# Nixie.net
KiCad netlist of a schematic drawn in EAGLE
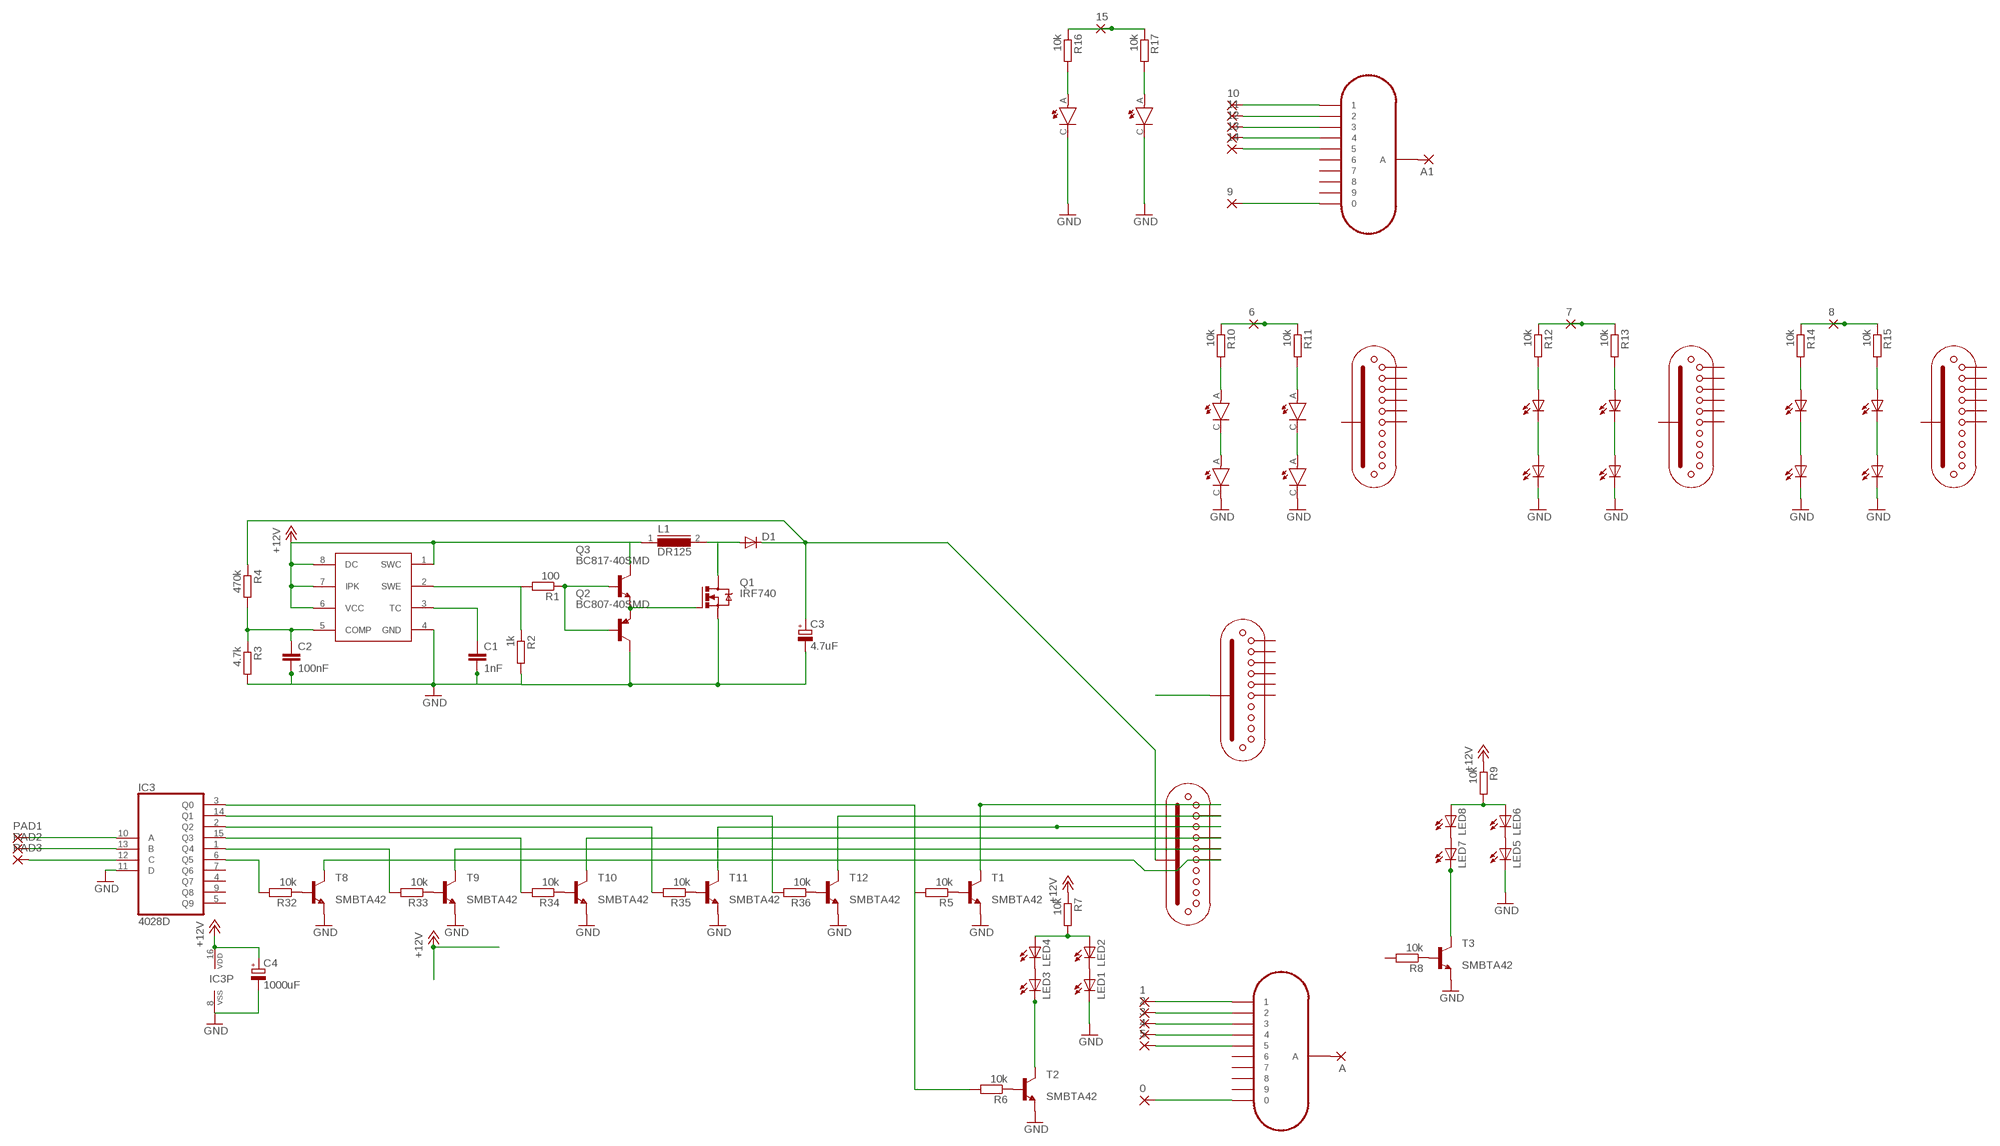
[diagram p0: schematic, sheet 1]

(export (version "E")
  (design (tool "Eeschema 10.0.6"))
  (components
    (comp (ref "0")
      (value "SMD2")
      (footprint "eagle-import:SMD1,27-2,54")
      (libsource (lib "eagle-import") (part "SMD2"))
    )
    (comp (ref "1")
      (value "SMD2")
      (footprint "eagle-import:SMD1,27-2,54")
      (libsource (lib "eagle-import") (part "SMD2"))
    )
    (comp (ref "2")
      (value "SMD2")
      (footprint "eagle-import:SMD1,27-2,54")
      (libsource (lib "eagle-import") (part "SMD2"))
    )
    (comp (ref "3")
      (value "SMD2")
      (footprint "eagle-import:SMD1,27-2,54")
      (libsource (lib "eagle-import") (part "SMD2"))
    )
    (comp (ref "4")
      (value "SMD2")
      (footprint "eagle-import:SMD1,27-2,54")
      (libsource (lib "eagle-import") (part "SMD2"))
    )
    (comp (ref "5")
      (value "SMD2")
      (footprint "eagle-import:SMD1,27-2,54")
      (libsource (lib "eagle-import") (part "SMD2"))
    )
    (comp (ref "6")
      (value "SMD2")
      (footprint "eagle-import:SMD1,27-2,54")
      (libsource (lib "eagle-import") (part "SMD2"))
    )
    (comp (ref "7")
      (value "SMD2")
      (footprint "eagle-import:SMD1,27-2,54")
      (libsource (lib "eagle-import") (part "SMD2"))
    )
    (comp (ref "8")
      (value "SMD2")
      (footprint "eagle-import:SMD1,27-2,54")
      (libsource (lib "eagle-import") (part "SMD2"))
    )
    (comp (ref "9")
      (value "SMD2")
      (footprint "eagle-import:SMD1,27-2,54")
      (libsource (lib "eagle-import") (part "SMD2"))
    )
    (comp (ref "10")
      (value "SMD2")
      (footprint "eagle-import:SMD1,27-2,54")
      (libsource (lib "eagle-import") (part "SMD2"))
    )
    (comp (ref "11")
      (value "SMD2")
      (footprint "eagle-import:SMD1,27-2,54")
      (libsource (lib "eagle-import") (part "SMD2"))
    )
    (comp (ref "12")
      (value "SMD2")
      (footprint "eagle-import:SMD1,27-2,54")
      (libsource (lib "eagle-import") (part "SMD2"))
    )
    (comp (ref "13")
      (value "SMD2")
      (footprint "eagle-import:SMD1,27-2,54")
      (libsource (lib "eagle-import") (part "SMD2"))
    )
    (comp (ref "14")
      (value "SMD2")
      (footprint "eagle-import:SMD1,27-2,54")
      (libsource (lib "eagle-import") (part "SMD2"))
    )
    (comp (ref "15")
      (value "SMD2")
      (footprint "eagle-import:SMD1,27-2,54")
      (libsource (lib "eagle-import") (part "SMD2"))
    )
    (comp (ref "A")
      (value "SMD2")
      (footprint "eagle-import:SMD1,27-2,54")
      (libsource (lib "eagle-import") (part "SMD2"))
    )
    (comp (ref "A1")
      (value "SMD2")
      (footprint "eagle-import:SMD1,27-2,54")
      (libsource (lib "eagle-import") (part "SMD2"))
    )
    (comp (ref "C1")
      (value "1nF")
      (footprint "eagle-import:C0805K")
      (libsource (lib "eagle-import") (part "C-EUC0805K"))
    )
    (comp (ref "C2")
      (value "100nF")
      (footprint "eagle-import:C0805K")
      (libsource (lib "eagle-import") (part "C-EUC0805K"))
    )
    (comp (ref "C3")
      (value "4.7uF")
      (footprint "eagle-import:E5-10,5")
      (libsource (lib "eagle-import") (part "CPOL-EUE5-10.5"))
    )
    (comp (ref "C4")
      (value "1000uF")
      (footprint "eagle-import:E5-10,5")
      (libsource (lib "eagle-import") (part "CPOL-EUE5-10.5"))
    )
    (comp (ref "D1")
      (value "DIODE-DO214AC")
      (footprint "eagle-import:DO214AC")
      (libsource (lib "eagle-import") (part "DIODE-DO214AC"))
    )
    (comp (ref "IC3")
      (value "4028D")
      (footprint "eagle-import:SO16")
      (libsource (lib "eagle-import") (part "4028D"))
    )
    (comp (ref "L1")
      (value "DR125")
      (footprint "eagle-import:DR125")
      (libsource (lib "eagle-import") (part "DR125"))
    )
    (comp (ref "LED1")
      (value "LED3MM")
      (footprint "eagle-import:LED3MM")
      (libsource (lib "eagle-import") (part "LED3MM"))
    )
    (comp (ref "LED2")
      (value "LED3MM")
      (footprint "eagle-import:LED3MM")
      (libsource (lib "eagle-import") (part "LED3MM"))
    )
    (comp (ref "LED3")
      (value "LED3MM")
      (footprint "eagle-import:LED3MM")
      (libsource (lib "eagle-import") (part "LED3MM"))
    )
    (comp (ref "LED4")
      (value "LED3MM")
      (footprint "eagle-import:LED3MM")
      (libsource (lib "eagle-import") (part "LED3MM"))
    )
    (comp (ref "LED5")
      (value "LED3MM")
      (footprint "eagle-import:LED3MM")
      (libsource (lib "eagle-import") (part "LED3MM"))
    )
    (comp (ref "LED6")
      (value "LED3MM")
      (footprint "eagle-import:LED3MM")
      (libsource (lib "eagle-import") (part "LED3MM"))
    )
    (comp (ref "LED7")
      (value "LED3MM")
      (footprint "eagle-import:LED3MM")
      (libsource (lib "eagle-import") (part "LED3MM"))
    )
    (comp (ref "LED8")
      (value "LED3MM")
      (footprint "eagle-import:LED3MM")
      (libsource (lib "eagle-import") (part "LED3MM"))
    )
    (comp (ref "LED9")
      (value "LED_PLCC6")
      (footprint "eagle-import:PLCC6")
      (libsource (lib "eagle-import") (part "LED_PLCC6"))
    )
    (comp (ref "LED10")
      (value "LED_PLCC6")
      (footprint "eagle-import:PLCC6")
      (libsource (lib "eagle-import") (part "LED_PLCC6"))
    )
    (comp (ref "LED11")
      (value "LED_PLCC6")
      (footprint "eagle-import:PLCC6")
      (libsource (lib "eagle-import") (part "LED_PLCC6"))
    )
    (comp (ref "LED12")
      (value "LED_PLCC6")
      (footprint "eagle-import:PLCC6")
      (libsource (lib "eagle-import") (part "LED_PLCC6"))
    )
    (comp (ref "LED13")
      (value "LED_LRTB_G6TG")
      (footprint "eagle-import:PLCC6")
      (libsource (lib "eagle-import") (part "LED_LRTB_G6TG"))
    )
    (comp (ref "LED14")
      (value "LED_LRTB_G6TG")
      (footprint "eagle-import:PLCC6")
      (libsource (lib "eagle-import") (part "LED_LRTB_G6TG"))
    )
    (comp (ref "N1")
      (value "IN-12A-IN-12")
      (footprint "eagle-import:IN-12")
      (libsource (lib "eagle-import") (part "IN-12A-IN-12"))
    )
    (comp (ref "N2")
      (value "IN-12A-IN-12")
      (footprint "eagle-import:IN-12")
      (libsource (lib "eagle-import") (part "IN-12A-IN-12"))
    )
    (comp (ref "PAD1")
      (value "1,6/0,8")
      (footprint "eagle-import:1,6_0,8")
      (libsource (lib "eagle-import") (part "1,6/0,8"))
    )
    (comp (ref "PAD2")
      (value "1,6/0,8")
      (footprint "eagle-import:1,6_0,8")
      (libsource (lib "eagle-import") (part "1,6/0,8"))
    )
    (comp (ref "PAD3")
      (value "1,6/0,8")
      (footprint "eagle-import:1,6_0,8")
      (libsource (lib "eagle-import") (part "1,6/0,8"))
    )
    (comp (ref "Q1")
      (value "IRF740")
      (footprint "eagle-import:TO220BV")
      (libsource (lib "eagle-import") (part "IRF740"))
    )
    (comp (ref "Q2")
      (value "BC807-40SMD")
      (footprint "eagle-import:SOT23-BEC")
      (libsource (lib "eagle-import") (part "BC807SMD-40"))
    )
    (comp (ref "Q3")
      (value "BC817-40SMD")
      (footprint "eagle-import:SOT23-BEC")
      (libsource (lib "eagle-import") (part "BC817SMD-40"))
    )
    (comp (ref "R1")
      (value "100")
      (footprint "eagle-import:R0805")
      (libsource (lib "eagle-import") (part "R-EU_R0805"))
    )
    (comp (ref "R2")
      (value "1k")
      (footprint "eagle-import:R0805")
      (libsource (lib "eagle-import") (part "R-EU_R0805"))
    )
    (comp (ref "R3")
      (value "4.7k")
      (footprint "eagle-import:R0805")
      (libsource (lib "eagle-import") (part "R-EU_R0805"))
    )
    (comp (ref "R4")
      (value "470k")
      (footprint "eagle-import:R0805")
      (libsource (lib "eagle-import") (part "R-EU_R0805"))
    )
    (comp (ref "R5")
      (value "10k")
      (footprint "eagle-import:R0805")
      (libsource (lib "eagle-import") (part "R-EU_R0805"))
    )
    (comp (ref "R6")
      (value "10k")
      (footprint "eagle-import:R0805")
      (libsource (lib "eagle-import") (part "R-EU_R0805"))
    )
    (comp (ref "R7")
      (value "10k")
      (footprint "eagle-import:R0805")
      (libsource (lib "eagle-import") (part "R-EU_R0805"))
    )
    (comp (ref "R8")
      (value "10k")
      (footprint "eagle-import:R0805")
      (libsource (lib "eagle-import") (part "R-EU_R0805"))
    )
    (comp (ref "R9")
      (value "10k")
      (footprint "eagle-import:R0805")
      (libsource (lib "eagle-import") (part "R-EU_R0805"))
    )
    (comp (ref "R10")
      (value "10k")
      (footprint "eagle-import:R0805")
      (libsource (lib "eagle-import") (part "R-EU_R0805"))
    )
    (comp (ref "R11")
      (value "10k")
      (footprint "eagle-import:R0805")
      (libsource (lib "eagle-import") (part "R-EU_R0805"))
    )
    (comp (ref "R12")
      (value "10k")
      (footprint "eagle-import:R0805")
      (libsource (lib "eagle-import") (part "R-EU_R0805"))
    )
    (comp (ref "R13")
      (value "10k")
      (footprint "eagle-import:R0805")
      (libsource (lib "eagle-import") (part "R-EU_R0805"))
    )
    (comp (ref "R14")
      (value "10k")
      (footprint "eagle-import:R0805")
      (libsource (lib "eagle-import") (part "R-EU_R0805"))
    )
    (comp (ref "R15")
      (value "10k")
      (footprint "eagle-import:R0805")
      (libsource (lib "eagle-import") (part "R-EU_R0805"))
    )
    (comp (ref "R16")
      (value "10k")
      (footprint "eagle-import:R0805")
      (libsource (lib "eagle-import") (part "R-EU_R0805"))
    )
    (comp (ref "R17")
      (value "10k")
      (footprint "eagle-import:R0805")
      (libsource (lib "eagle-import") (part "R-EU_R0805"))
    )
    (comp (ref "R32")
      (value "10k")
      (footprint "eagle-import:R0805")
      (libsource (lib "eagle-import") (part "R-EU_R0805"))
    )
    (comp (ref "R33")
      (value "10k")
      (footprint "eagle-import:R0805")
      (libsource (lib "eagle-import") (part "R-EU_R0805"))
    )
    (comp (ref "R34")
      (value "10k")
      (footprint "eagle-import:R0805")
      (libsource (lib "eagle-import") (part "R-EU_R0805"))
    )
    (comp (ref "R35")
      (value "10k")
      (footprint "eagle-import:R0805")
      (libsource (lib "eagle-import") (part "R-EU_R0805"))
    )
    (comp (ref "R36")
      (value "10k")
      (footprint "eagle-import:R0805")
      (libsource (lib "eagle-import") (part "R-EU_R0805"))
    )
    (comp (ref "T1")
      (value "MMBTA42LT1-NPN-SOT23-BEC")
      (footprint "eagle-import:SOT23-BEC")
      (fields (field (name "T") "SMBTA42"))
      (libsource (lib "eagle-import") (part "-NPN-SOT23-BECMMBTA42LT1"))
    )
    (comp (ref "T2")
      (value "MMBTA42LT1-NPN-SOT23-BEC")
      (footprint "eagle-import:SOT23-BEC")
      (fields (field (name "T") "SMBTA42"))
      (libsource (lib "eagle-import") (part "-NPN-SOT23-BECMMBTA42LT1"))
    )
    (comp (ref "T3")
      (value "MMBTA42LT1-NPN-SOT23-BEC")
      (footprint "eagle-import:SOT23-BEC")
      (fields (field (name "T") "SMBTA42"))
      (libsource (lib "eagle-import") (part "-NPN-SOT23-BECMMBTA42LT1"))
    )
    (comp (ref "T8")
      (value "MMBTA42LT1-NPN-SOT23-BEC")
      (footprint "eagle-import:SOT23-BEC")
      (fields (field (name "T") "SMBTA42"))
      (libsource (lib "eagle-import") (part "-NPN-SOT23-BECMMBTA42LT1"))
    )
    (comp (ref "T9")
      (value "MMBTA42LT1-NPN-SOT23-BEC")
      (footprint "eagle-import:SOT23-BEC")
      (fields (field (name "T") "SMBTA42"))
      (libsource (lib "eagle-import") (part "-NPN-SOT23-BECMMBTA42LT1"))
    )
    (comp (ref "T10")
      (value "MMBTA42LT1-NPN-SOT23-BEC")
      (footprint "eagle-import:SOT23-BEC")
      (fields (field (name "T") "SMBTA42"))
      (libsource (lib "eagle-import") (part "-NPN-SOT23-BECMMBTA42LT1"))
    )
    (comp (ref "T11")
      (value "MMBTA42LT1-NPN-SOT23-BEC")
      (footprint "eagle-import:SOT23-BEC")
      (fields (field (name "T") "SMBTA42"))
      (libsource (lib "eagle-import") (part "-NPN-SOT23-BECMMBTA42LT1"))
    )
    (comp (ref "T12")
      (value "MMBTA42LT1-NPN-SOT23-BEC")
      (footprint "eagle-import:SOT23-BEC")
      (fields (field (name "T") "SMBTA42"))
      (libsource (lib "eagle-import") (part "-NPN-SOT23-BECMMBTA42LT1"))
    )
    (comp (ref "U$1")
      (value "ZM1020")
      (footprint "eagle-import:ZM1020")
      (libsource (lib "eagle-import") (part "ZM1020"))
    )
    (comp (ref "U$2")
      (value "MC33063/MC34063D")
      (footprint "eagle-import:SO08")
      (libsource (lib "eagle-import") (part "MC33063/MC34063D"))
    )
    (comp (ref "U$3")
      (value "ZM1020")
      (footprint "eagle-import:ZM1020")
      (libsource (lib "eagle-import") (part "ZM1020"))
    )
    (comp (ref "U$4")
      (value "PLCC2")
      (footprint "eagle-import:PLCC2")
      (libsource (lib "eagle-import") (part "PLCC2"))
    )
    (comp (ref "U$5")
      (value "PLCC2")
      (footprint "eagle-import:PLCC2")
      (libsource (lib "eagle-import") (part "PLCC2"))
    )
    (comp (ref "U$6")
      (value "ZM1020")
      (footprint "eagle-import:ZM1020")
      (libsource (lib "eagle-import") (part "ZM1020"))
    )
    (comp (ref "U$7")
      (value "PLCC2")
      (footprint "eagle-import:PLCC2")
      (libsource (lib "eagle-import") (part "PLCC2"))
    )
    (comp (ref "U$8")
      (value "PLCC2")
      (footprint "eagle-import:PLCC2")
      (libsource (lib "eagle-import") (part "PLCC2"))
    )
    (comp (ref "U$9")
      (value "ZM1020")
      (footprint "eagle-import:ZM1020")
      (libsource (lib "eagle-import") (part "ZM1020"))
    )
    (comp (ref "U$10")
      (value "PLCC2")
      (footprint "eagle-import:PLCC2")
      (libsource (lib "eagle-import") (part "PLCC2"))
    )
    (comp (ref "U$11")
      (value "ZM1020")
      (footprint "eagle-import:ZM1020")
      (libsource (lib "eagle-import") (part "ZM1020"))
    )
    (comp (ref "U$12")
      (value "PLCC2")
      (footprint "eagle-import:PLCC2")
      (libsource (lib "eagle-import") (part "PLCC2"))
    )
  )
  (nets
    (net (code "1") (name "+12V") (class "Default")
      (node (ref "C4") (pin "+") (pinfunction "+_+") (pintype "passive"))
      (node (ref "IC3") (pin "16") (pinfunction "VDD_16") (pintype "power_in"))
      (node (ref "L1") (pin "1") (pinfunction "1_1") (pintype "passive"))
      (node (ref "Q3") (pin "C") (pinfunction "C_C") (pintype "passive"))
      (node (ref "R7") (pin "1") (pinfunction "1_1") (pintype "passive"))
      (node (ref "R9") (pin "1") (pinfunction "1_1") (pintype "passive"))
      (node (ref "U$2") (pin "1") (pinfunction "SWC_1") (pintype "input"))
      (node (ref "U$2") (pin "6") (pinfunction "VCC_6") (pintype "power_in"))
      (node (ref "U$2") (pin "7") (pinfunction "IPK_7") (pintype "bidirectional"))
      (node (ref "U$2") (pin "8") (pinfunction "DC_8") (pintype "input"))
    )
    (net (code "2") (name "GND") (class "Default")
      (node (ref "C1") (pin "2") (pinfunction "2_2") (pintype "passive"))
      (node (ref "C2") (pin "2") (pinfunction "2_2") (pintype "passive"))
      (node (ref "C3") (pin "-") (pinfunction "-_-") (pintype "passive"))
      (node (ref "C4") (pin "-") (pinfunction "-_-") (pintype "passive"))
      (node (ref "IC3") (pin "11") (pinfunction "D_11") (pintype "input"))
      (node (ref "IC3") (pin "8") (pinfunction "VSS_8") (pintype "power_in"))
      (node (ref "LED1") (pin "K") (pinfunction "C_K") (pintype "passive"))
      (node (ref "LED10") (pin "C3") (pinfunction "C_C3") (pintype "passive"))
      (node (ref "LED12") (pin "C3") (pinfunction "C_C3") (pintype "passive"))
      (node (ref "LED14") (pin "C2") (pinfunction "C_C2") (pintype "passive"))
      (node (ref "LED14") (pin "C3") (pinfunction "C_C3") (pintype "passive"))
      (node (ref "LED5") (pin "K") (pinfunction "C_K") (pintype "passive"))
      (node (ref "Q1") (pin "S") (pinfunction "S_S") (pintype "passive"))
      (node (ref "Q2") (pin "C") (pinfunction "C_C") (pintype "passive"))
      (node (ref "R2") (pin "2") (pinfunction "2_2") (pintype "passive"))
      (node (ref "R3") (pin "2") (pinfunction "2_2") (pintype "passive"))
      (node (ref "T1") (pin "E") (pinfunction "E_E") (pintype "passive"))
      (node (ref "T10") (pin "E") (pinfunction "E_E") (pintype "passive"))
      (node (ref "T11") (pin "E") (pinfunction "E_E") (pintype "passive"))
      (node (ref "T12") (pin "E") (pinfunction "E_E") (pintype "passive"))
      (node (ref "T2") (pin "E") (pinfunction "E_E") (pintype "passive"))
      (node (ref "T3") (pin "E") (pinfunction "E_E") (pintype "passive"))
      (node (ref "T8") (pin "E") (pinfunction "E_E") (pintype "passive"))
      (node (ref "T9") (pin "E") (pinfunction "E_E") (pintype "passive"))
      (node (ref "U$10") (pin "C") (pinfunction "C_C") (pintype "bidirectional"))
      (node (ref "U$12") (pin "C") (pinfunction "C_C") (pintype "bidirectional"))
      (node (ref "U$2") (pin "4") (pinfunction "GND_4") (pintype "power_in"))
      (node (ref "U$7") (pin "C") (pinfunction "C_C") (pintype "bidirectional"))
      (node (ref "U$8") (pin "C") (pinfunction "C_C") (pintype "bidirectional"))
    )
    (net (code "3") (name "Net-(0-P)") (class "Default")
      (node (ref "0") (pin "1") (pinfunction "P_1") (pintype "passive"))
      (node (ref "N1") (pin "0") (pinfunction "0_0") (pintype "bidirectional"))
    )
    (net (code "4") (name "Net-(1-P)") (class "Default")
      (node (ref "1") (pin "1") (pinfunction "P_1") (pintype "passive"))
      (node (ref "N1") (pin "1") (pinfunction "1_1") (pintype "bidirectional"))
    )
    (net (code "5") (name "Net-(2-P)") (class "Default")
      (node (ref "2") (pin "1") (pinfunction "P_1") (pintype "passive"))
      (node (ref "N1") (pin "2") (pinfunction "2_2") (pintype "bidirectional"))
    )
    (net (code "6") (name "Net-(3-P)") (class "Default")
      (node (ref "3") (pin "1") (pinfunction "P_1") (pintype "passive"))
      (node (ref "N1") (pin "3") (pinfunction "3_3") (pintype "bidirectional"))
    )
    (net (code "7") (name "Net-(4-P)") (class "Default")
      (node (ref "4") (pin "1") (pinfunction "P_1") (pintype "passive"))
      (node (ref "N1") (pin "4") (pinfunction "4_4") (pintype "bidirectional"))
    )
    (net (code "8") (name "Net-(5-P)") (class "Default")
      (node (ref "5") (pin "1") (pinfunction "P_1") (pintype "passive"))
      (node (ref "N1") (pin "5") (pinfunction "5_5") (pintype "bidirectional"))
    )
    (net (code "9") (name "Net-(6-P)") (class "Default")
      (node (ref "6") (pin "1") (pinfunction "P_1") (pintype "passive"))
      (node (ref "R10") (pin "1") (pinfunction "1_1") (pintype "passive"))
      (node (ref "R11") (pin "1") (pinfunction "1_1") (pintype "passive"))
    )
    (net (code "10") (name "Net-(7-P)") (class "Default")
      (node (ref "7") (pin "1") (pinfunction "P_1") (pintype "passive"))
      (node (ref "R12") (pin "1") (pinfunction "1_1") (pintype "passive"))
      (node (ref "R13") (pin "1") (pinfunction "1_1") (pintype "passive"))
    )
    (net (code "11") (name "Net-(8-P)") (class "Default")
      (node (ref "8") (pin "1") (pinfunction "P_1") (pintype "passive"))
      (node (ref "R14") (pin "1") (pinfunction "1_1") (pintype "passive"))
      (node (ref "R15") (pin "1") (pinfunction "1_1") (pintype "passive"))
    )
    (net (code "12") (name "Net-(9-P)") (class "Default")
      (node (ref "9") (pin "1") (pinfunction "P_1") (pintype "passive"))
      (node (ref "N2") (pin "0") (pinfunction "0_0") (pintype "bidirectional"))
    )
    (net (code "13") (name "Net-(10-P)") (class "Default")
      (node (ref "10") (pin "1") (pinfunction "P_1") (pintype "passive"))
      (node (ref "N2") (pin "1") (pinfunction "1_1") (pintype "bidirectional"))
    )
    (net (code "14") (name "Net-(11-P)") (class "Default")
      (node (ref "11") (pin "1") (pinfunction "P_1") (pintype "passive"))
      (node (ref "N2") (pin "2") (pinfunction "2_2") (pintype "bidirectional"))
    )
    (net (code "15") (name "Net-(12-P)") (class "Default")
      (node (ref "12") (pin "1") (pinfunction "P_1") (pintype "passive"))
      (node (ref "N2") (pin "3") (pinfunction "3_3") (pintype "bidirectional"))
    )
    (net (code "16") (name "Net-(13-P)") (class "Default")
      (node (ref "13") (pin "1") (pinfunction "P_1") (pintype "passive"))
      (node (ref "N2") (pin "4") (pinfunction "4_4") (pintype "bidirectional"))
    )
    (net (code "17") (name "Net-(14-P)") (class "Default")
      (node (ref "14") (pin "1") (pinfunction "P_1") (pintype "passive"))
      (node (ref "N2") (pin "5") (pinfunction "5_5") (pintype "bidirectional"))
    )
    (net (code "18") (name "Net-(15-P)") (class "Default")
      (node (ref "15") (pin "1") (pinfunction "P_1") (pintype "passive"))
      (node (ref "R16") (pin "1") (pinfunction "1_1") (pintype "passive"))
      (node (ref "R17") (pin "1") (pinfunction "1_1") (pintype "passive"))
    )
    (net (code "19") (name "Net-(A-P)") (class "Default")
      (node (ref "A") (pin "1") (pinfunction "P_1") (pintype "passive"))
      (node (ref "N1") (pin "A") (pinfunction "A_A") (pintype "bidirectional"))
    )
    (net (code "20") (name "Net-(A1-P)") (class "Default")
      (node (ref "A1") (pin "1") (pinfunction "P_1") (pintype "passive"))
      (node (ref "N2") (pin "A") (pinfunction "A_A") (pintype "bidirectional"))
    )
    (net (code "21") (name "Net-(D1-PadA)") (class "Default")
      (node (ref "D1") (pin "A") (pinfunction "A_A") (pintype "passive"))
      (node (ref "L1") (pin "2") (pinfunction "2_2") (pintype "passive"))
      (node (ref "Q1") (pin "D") (pinfunction "D_D") (pintype "passive"))
    )
    (net (code "22") (name "Net-(IC3A-A)") (class "Default")
      (node (ref "IC3") (pin "10") (pinfunction "A_10") (pintype "input"))
      (node (ref "PAD1") (pin "1") (pinfunction "P_1") (pintype "passive"))
    )
    (net (code "23") (name "Net-(IC3A-B)") (class "Default")
      (node (ref "IC3") (pin "13") (pinfunction "B_13") (pintype "input"))
      (node (ref "PAD2") (pin "1") (pinfunction "P_1") (pintype "passive"))
    )
    (net (code "24") (name "Net-(IC3A-C)") (class "Default")
      (node (ref "IC3") (pin "12") (pinfunction "C_12") (pintype "input"))
      (node (ref "PAD3") (pin "1") (pinfunction "P_1") (pintype "passive"))
    )
    (net (code "25") (name "Net-(IC3A-Q0)") (class "Default")
      (node (ref "IC3") (pin "3") (pinfunction "Q0_3") (pintype "output"))
      (node (ref "R5") (pin "2") (pinfunction "2_2") (pintype "passive"))
      (node (ref "R6") (pin "2") (pinfunction "2_2") (pintype "passive"))
    )
    (net (code "26") (name "Net-(IC3A-Q1)") (class "Default")
      (node (ref "IC3") (pin "14") (pinfunction "Q1_14") (pintype "output"))
      (node (ref "R36") (pin "2") (pinfunction "2_2") (pintype "passive"))
    )
    (net (code "27") (name "Net-(IC3A-Q2)") (class "Default")
      (node (ref "IC3") (pin "2") (pinfunction "Q2_2") (pintype "output"))
      (node (ref "R35") (pin "2") (pinfunction "2_2") (pintype "passive"))
    )
    (net (code "28") (name "Net-(IC3A-Q3)") (class "Default")
      (node (ref "IC3") (pin "15") (pinfunction "Q3_15") (pintype "output"))
      (node (ref "R34") (pin "2") (pinfunction "2_2") (pintype "passive"))
    )
    (net (code "29") (name "Net-(IC3A-Q4)") (class "Default")
      (node (ref "IC3") (pin "1") (pinfunction "Q4_1") (pintype "output"))
      (node (ref "R33") (pin "2") (pinfunction "2_2") (pintype "passive"))
    )
    (net (code "30") (name "Net-(IC3A-Q5)") (class "Default")
      (node (ref "IC3") (pin "6") (pinfunction "Q5_6") (pintype "output"))
      (node (ref "R32") (pin "2") (pinfunction "2_2") (pintype "passive"))
    )
    (net (code "31") (name "Net-(LED2-C)") (class "Default")
      (node (ref "LED1") (pin "A") (pinfunction "A_A") (pintype "passive"))
      (node (ref "LED2") (pin "K") (pinfunction "C_K") (pintype "passive"))
    )
    (net (code "32") (name "Net-(LED2-PadA)") (class "Default")
      (node (ref "LED2") (pin "A") (pinfunction "A_A") (pintype "passive"))
      (node (ref "LED4") (pin "A") (pinfunction "A_A") (pintype "passive"))
      (node (ref "R7") (pin "2") (pinfunction "2_2") (pintype "passive"))
    )
    (net (code "33") (name "Net-(LED3-C)") (class "Default")
      (node (ref "LED3") (pin "K") (pinfunction "C_K") (pintype "passive"))
      (node (ref "T2") (pin "C") (pinfunction "C_C") (pintype "passive"))
    )
    (net (code "34") (name "Net-(LED4-C)") (class "Default")
      (node (ref "LED3") (pin "A") (pinfunction "A_A") (pintype "passive"))
      (node (ref "LED4") (pin "K") (pinfunction "C_K") (pintype "passive"))
    )
    (net (code "35") (name "Net-(LED6-C)") (class "Default")
      (node (ref "LED5") (pin "A") (pinfunction "A_A") (pintype "passive"))
      (node (ref "LED6") (pin "K") (pinfunction "C_K") (pintype "passive"))
    )
    (net (code "36") (name "Net-(LED6-PadA)") (class "Default")
      (node (ref "LED6") (pin "A") (pinfunction "A_A") (pintype "passive"))
      (node (ref "LED8") (pin "A") (pinfunction "A_A") (pintype "passive"))
      (node (ref "R9") (pin "2") (pinfunction "2_2") (pintype "passive"))
    )
    (net (code "37") (name "Net-(LED7-C)") (class "Default")
      (node (ref "LED7") (pin "K") (pinfunction "C_K") (pintype "passive"))
      (node (ref "T3") (pin "C") (pinfunction "C_C") (pintype "passive"))
    )
    (net (code "38") (name "Net-(LED8-C)") (class "Default")
      (node (ref "LED7") (pin "A") (pinfunction "A_A") (pintype "passive"))
      (node (ref "LED8") (pin "K") (pinfunction "C_K") (pintype "passive"))
    )
    (net (code "39") (name "Net-(LED9-A)") (class "Default")
      (node (ref "LED9") (pin "A3") (pinfunction "A_A3") (pintype "passive"))
      (node (ref "R12") (pin "2") (pinfunction "2_2") (pintype "passive"))
    )
    (net (code "40") (name "Net-(LED10-A)") (class "Default")
      (node (ref "LED10") (pin "A3") (pinfunction "A_A3") (pintype "passive"))
      (node (ref "LED9") (pin "C3") (pinfunction "C_C3") (pintype "passive"))
    )
    (net (code "41") (name "Net-(LED11-A)") (class "Default")
      (node (ref "LED11") (pin "A3") (pinfunction "A_A3") (pintype "passive"))
      (node (ref "R13") (pin "2") (pinfunction "2_2") (pintype "passive"))
    )
    (net (code "42") (name "Net-(LED11-C)") (class "Default")
      (node (ref "LED11") (pin "C3") (pinfunction "C_C3") (pintype "passive"))
      (node (ref "LED12") (pin "A3") (pinfunction "A_A3") (pintype "passive"))
    )
    (net (code "43") (name "Net-(LED13A-A)") (class "Default")
      (node (ref "LED13") (pin "A3") (pinfunction "A_A3") (pintype "passive"))
      (node (ref "R15") (pin "2") (pinfunction "2_2") (pintype "passive"))
    )
    (net (code "44") (name "Net-(LED13A-C)") (class "Default")
      (node (ref "LED13") (pin "C3") (pinfunction "C_C3") (pintype "passive"))
      (node (ref "LED14") (pin "A3") (pinfunction "A_A3") (pintype "passive"))
    )
    (net (code "45") (name "Net-(LED13B-A)") (class "Default")
      (node (ref "LED13") (pin "A2") (pinfunction "A_A2") (pintype "passive"))
      (node (ref "R14") (pin "2") (pinfunction "2_2") (pintype "passive"))
    )
    (net (code "46") (name "Net-(LED13B-C)") (class "Default")
      (node (ref "LED13") (pin "C2") (pinfunction "C_C2") (pintype "passive"))
      (node (ref "LED14") (pin "A2") (pinfunction "A_A2") (pintype "passive"))
    )
    (net (code "47") (name "Net-(Q1-PadG)") (class "Default")
      (node (ref "Q1") (pin "G") (pinfunction "G_G") (pintype "passive"))
      (node (ref "Q2") (pin "E") (pinfunction "E_E") (pintype "passive"))
      (node (ref "Q3") (pin "E") (pinfunction "E_E") (pintype "passive"))
    )
    (net (code "48") (name "Net-(Q2-PadB)") (class "Default")
      (node (ref "Q2") (pin "B") (pinfunction "B_B") (pintype "passive"))
      (node (ref "Q3") (pin "B") (pinfunction "B_B") (pintype "passive"))
      (node (ref "R1") (pin "1") (pinfunction "1_1") (pintype "passive"))
    )
    (net (code "49") (name "Net-(R5-Pad1)") (class "Default")
      (node (ref "R5") (pin "1") (pinfunction "1_1") (pintype "passive"))
      (node (ref "T1") (pin "B") (pinfunction "B_B") (pintype "passive"))
    )
    (net (code "50") (name "Net-(R6-Pad1)") (class "Default")
      (node (ref "R6") (pin "1") (pinfunction "1_1") (pintype "passive"))
      (node (ref "T2") (pin "B") (pinfunction "B_B") (pintype "passive"))
    )
    (net (code "51") (name "Net-(R8-Pad1)") (class "Default")
      (node (ref "R8") (pin "1") (pinfunction "1_1") (pintype "passive"))
      (node (ref "T3") (pin "B") (pinfunction "B_B") (pintype "passive"))
    )
    (net (code "52") (name "Net-(R10-Pad2)") (class "Default")
      (node (ref "R10") (pin "2") (pinfunction "2_2") (pintype "passive"))
      (node (ref "U$4") (pin "A") (pinfunction "A_A") (pintype "bidirectional"))
    )
    (net (code "53") (name "Net-(R11-Pad2)") (class "Default")
      (node (ref "R11") (pin "2") (pinfunction "2_2") (pintype "passive"))
      (node (ref "U$5") (pin "A") (pinfunction "A_A") (pintype "bidirectional"))
    )
    (net (code "54") (name "Net-(R16-Pad2)") (class "Default")
      (node (ref "R16") (pin "2") (pinfunction "2_2") (pintype "passive"))
      (node (ref "U$10") (pin "A") (pinfunction "A_A") (pintype "bidirectional"))
    )
    (net (code "55") (name "Net-(R17-Pad2)") (class "Default")
      (node (ref "R17") (pin "2") (pinfunction "2_2") (pintype "passive"))
      (node (ref "U$12") (pin "A") (pinfunction "A_A") (pintype "bidirectional"))
    )
    (net (code "56") (name "Net-(R32-Pad1)") (class "Default")
      (node (ref "R32") (pin "1") (pinfunction "1_1") (pintype "passive"))
      (node (ref "T8") (pin "B") (pinfunction "B_B") (pintype "passive"))
    )
    (net (code "57") (name "Net-(R33-Pad1)") (class "Default")
      (node (ref "R33") (pin "1") (pinfunction "1_1") (pintype "passive"))
      (node (ref "T9") (pin "B") (pinfunction "B_B") (pintype "passive"))
    )
    (net (code "58") (name "Net-(R34-Pad1)") (class "Default")
      (node (ref "R34") (pin "1") (pinfunction "1_1") (pintype "passive"))
      (node (ref "T10") (pin "B") (pinfunction "B_B") (pintype "passive"))
    )
    (net (code "59") (name "Net-(R35-Pad1)") (class "Default")
      (node (ref "R35") (pin "1") (pinfunction "1_1") (pintype "passive"))
      (node (ref "T11") (pin "B") (pinfunction "B_B") (pintype "passive"))
    )
    (net (code "60") (name "Net-(R36-Pad1)") (class "Default")
      (node (ref "R36") (pin "1") (pinfunction "1_1") (pintype "passive"))
      (node (ref "T12") (pin "B") (pinfunction "B_B") (pintype "passive"))
    )
    (net (code "61") (name "Net-(T8-PadC)") (class "Default")
      (node (ref "T8") (pin "C") (pinfunction "C_C") (pintype "passive"))
      (node (ref "U$1") (pin "5") (pinfunction "5_5") (pintype "bidirectional"))
    )
    (net (code "62") (name "Net-(T9-PadC)") (class "Default")
      (node (ref "T9") (pin "C") (pinfunction "C_C") (pintype "passive"))
      (node (ref "U$1") (pin "4") (pinfunction "4_4") (pintype "bidirectional"))
    )
    (net (code "63") (name "Net-(T10-PadC)") (class "Default")
      (node (ref "T10") (pin "C") (pinfunction "C_C") (pintype "passive"))
      (node (ref "U$1") (pin "3") (pinfunction "3_3") (pintype "bidirectional"))
    )
    (net (code "64") (name "Net-(T11-PadC)") (class "Default")
      (node (ref "T11") (pin "C") (pinfunction "C_C") (pintype "passive"))
      (node (ref "U$1") (pin "2") (pinfunction "2_2") (pintype "bidirectional"))
    )
    (net (code "65") (name "Net-(T12-PadC)") (class "Default")
      (node (ref "T12") (pin "C") (pinfunction "C_C") (pintype "passive"))
      (node (ref "U$1") (pin "1") (pinfunction "1_1") (pintype "bidirectional"))
    )
    (net (code "66") (name "Net-(U$1-0)") (class "Default")
      (node (ref "T1") (pin "C") (pinfunction "C_C") (pintype "passive"))
      (node (ref "U$1") (pin "11") (pinfunction "0_11") (pintype "bidirectional"))
    )
    (net (code "67") (name "Net-(U$1-A)") (class "Default")
      (node (ref "C3") (pin "+") (pinfunction "+_+") (pintype "passive"))
      (node (ref "D1") (pin "C") (pinfunction "C_C") (pintype "passive"))
      (node (ref "R4") (pin "1") (pinfunction "1_1") (pintype "passive"))
      (node (ref "U$1") (pin "12") (pinfunction "A_12") (pintype "bidirectional"))
    )
    (net (code "68") (name "Net-(U$2-COMP)") (class "Default")
      (node (ref "C2") (pin "1") (pinfunction "1_1") (pintype "passive"))
      (node (ref "R3") (pin "1") (pinfunction "1_1") (pintype "passive"))
      (node (ref "R4") (pin "2") (pinfunction "2_2") (pintype "passive"))
      (node (ref "U$2") (pin "5") (pinfunction "COMP_5") (pintype "input"))
    )
    (net (code "69") (name "Net-(U$2-SWE)") (class "Default")
      (node (ref "R1") (pin "2") (pinfunction "2_2") (pintype "passive"))
      (node (ref "R2") (pin "1") (pinfunction "1_1") (pintype "passive"))
      (node (ref "U$2") (pin "2") (pinfunction "SWE_2") (pintype "input"))
    )
    (net (code "70") (name "Net-(U$2-TC)") (class "Default")
      (node (ref "C1") (pin "1") (pinfunction "1_1") (pintype "passive"))
      (node (ref "U$2") (pin "3") (pinfunction "TC_3") (pintype "input"))
    )
    (net (code "71") (name "Net-(U$4-PadC)") (class "Default")
      (node (ref "U$4") (pin "C") (pinfunction "C_C") (pintype "bidirectional"))
      (node (ref "U$7") (pin "A") (pinfunction "A_A") (pintype "bidirectional"))
    )
    (net (code "72") (name "Net-(U$5-PadC)") (class "Default")
      (node (ref "U$5") (pin "C") (pinfunction "C_C") (pintype "bidirectional"))
      (node (ref "U$8") (pin "A") (pinfunction "A_A") (pintype "bidirectional"))
    )
    (net (code "73") (name "unconnected-(IC3A-Q6-Pad7)") (class "Default")
      (node (ref "IC3") (pin "7") (pinfunction "Q6_7") (pintype "output"))
    )
    (net (code "74") (name "unconnected-(IC3A-Q7-Pad4)") (class "Default")
      (node (ref "IC3") (pin "4") (pinfunction "Q7_4") (pintype "output"))
    )
    (net (code "75") (name "unconnected-(IC3A-Q8-Pad9)") (class "Default")
      (node (ref "IC3") (pin "9") (pinfunction "Q8_9") (pintype "output"))
    )
    (net (code "76") (name "unconnected-(IC3A-Q9-Pad5)") (class "Default")
      (node (ref "IC3") (pin "5") (pinfunction "Q9_5") (pintype "output"))
    )
    (net (code "77") (name "unconnected-(N1-Pad6)") (class "Default")
      (node (ref "N1") (pin "6") (pinfunction "6_6") (pintype "bidirectional"))
    )
    (net (code "78") (name "unconnected-(N1-Pad7)") (class "Default")
      (node (ref "N1") (pin "7") (pinfunction "7_7") (pintype "bidirectional"))
    )
    (net (code "79") (name "unconnected-(N1-Pad8)") (class "Default")
      (node (ref "N1") (pin "8") (pinfunction "8_8") (pintype "bidirectional"))
    )
    (net (code "80") (name "unconnected-(N1-Pad9)") (class "Default")
      (node (ref "N1") (pin "9") (pinfunction "9_9") (pintype "bidirectional"))
    )
    (net (code "81") (name "unconnected-(N2-Pad6)") (class "Default")
      (node (ref "N2") (pin "6") (pinfunction "6_6") (pintype "bidirectional"))
    )
    (net (code "82") (name "unconnected-(N2-Pad7)") (class "Default")
      (node (ref "N2") (pin "7") (pinfunction "7_7") (pintype "bidirectional"))
    )
    (net (code "83") (name "unconnected-(N2-Pad8)") (class "Default")
      (node (ref "N2") (pin "8") (pinfunction "8_8") (pintype "bidirectional"))
    )
    (net (code "84") (name "unconnected-(N2-Pad9)") (class "Default")
      (node (ref "N2") (pin "9") (pinfunction "9_9") (pintype "bidirectional"))
    )
    (net (code "85") (name "unconnected-(R8-Pad2)") (class "Default")
      (node (ref "R8") (pin "2") (pinfunction "2_2") (pintype "passive"))
    )
    (net (code "86") (name "unconnected-(U$3-0-Pad11)") (class "Default")
      (node (ref "U$3") (pin "11") (pinfunction "0_11") (pintype "bidirectional"))
    )
    (net (code "87") (name "unconnected-(U$3-A-Pad12)") (class "Default")
      (node (ref "U$3") (pin "12") (pinfunction "A_12") (pintype "bidirectional"))
    )
    (net (code "88") (name "unconnected-(U$3-Pad1)") (class "Default")
      (node (ref "U$3") (pin "1") (pinfunction "1_1") (pintype "bidirectional"))
    )
    (net (code "89") (name "unconnected-(U$3-Pad2)") (class "Default")
      (node (ref "U$3") (pin "2") (pinfunction "2_2") (pintype "bidirectional"))
    )
    (net (code "90") (name "unconnected-(U$3-Pad3)") (class "Default")
      (node (ref "U$3") (pin "3") (pinfunction "3_3") (pintype "bidirectional"))
    )
    (net (code "91") (name "unconnected-(U$3-Pad4)") (class "Default")
      (node (ref "U$3") (pin "4") (pinfunction "4_4") (pintype "bidirectional"))
    )
    (net (code "92") (name "unconnected-(U$3-Pad5)") (class "Default")
      (node (ref "U$3") (pin "5") (pinfunction "5_5") (pintype "bidirectional"))
    )
    (net (code "93") (name "unconnected-(U$6-0-Pad11)") (class "Default")
      (node (ref "U$6") (pin "11") (pinfunction "0_11") (pintype "bidirectional"))
    )
    (net (code "94") (name "unconnected-(U$6-A-Pad12)") (class "Default")
      (node (ref "U$6") (pin "12") (pinfunction "A_12") (pintype "bidirectional"))
    )
    (net (code "95") (name "unconnected-(U$6-Pad1)") (class "Default")
      (node (ref "U$6") (pin "1") (pinfunction "1_1") (pintype "bidirectional"))
    )
    (net (code "96") (name "unconnected-(U$6-Pad2)") (class "Default")
      (node (ref "U$6") (pin "2") (pinfunction "2_2") (pintype "bidirectional"))
    )
    (net (code "97") (name "unconnected-(U$6-Pad3)") (class "Default")
      (node (ref "U$6") (pin "3") (pinfunction "3_3") (pintype "bidirectional"))
    )
    (net (code "98") (name "unconnected-(U$6-Pad4)") (class "Default")
      (node (ref "U$6") (pin "4") (pinfunction "4_4") (pintype "bidirectional"))
    )
    (net (code "99") (name "unconnected-(U$6-Pad5)") (class "Default")
      (node (ref "U$6") (pin "5") (pinfunction "5_5") (pintype "bidirectional"))
    )
    (net (code "100") (name "unconnected-(U$9-0-Pad11)") (class "Default")
      (node (ref "U$9") (pin "11") (pinfunction "0_11") (pintype "bidirectional"))
    )
    (net (code "101") (name "unconnected-(U$9-A-Pad12)") (class "Default")
      (node (ref "U$9") (pin "12") (pinfunction "A_12") (pintype "bidirectional"))
    )
    (net (code "102") (name "unconnected-(U$9-Pad1)") (class "Default")
      (node (ref "U$9") (pin "1") (pinfunction "1_1") (pintype "bidirectional"))
    )
    (net (code "103") (name "unconnected-(U$9-Pad2)") (class "Default")
      (node (ref "U$9") (pin "2") (pinfunction "2_2") (pintype "bidirectional"))
    )
    (net (code "104") (name "unconnected-(U$9-Pad3)") (class "Default")
      (node (ref "U$9") (pin "3") (pinfunction "3_3") (pintype "bidirectional"))
    )
    (net (code "105") (name "unconnected-(U$9-Pad4)") (class "Default")
      (node (ref "U$9") (pin "4") (pinfunction "4_4") (pintype "bidirectional"))
    )
    (net (code "106") (name "unconnected-(U$9-Pad5)") (class "Default")
      (node (ref "U$9") (pin "5") (pinfunction "5_5") (pintype "bidirectional"))
    )
    (net (code "107") (name "unconnected-(U$11-0-Pad11)") (class "Default")
      (node (ref "U$11") (pin "11") (pinfunction "0_11") (pintype "bidirectional"))
    )
    (net (code "108") (name "unconnected-(U$11-A-Pad12)") (class "Default")
      (node (ref "U$11") (pin "12") (pinfunction "A_12") (pintype "bidirectional"))
    )
    (net (code "109") (name "unconnected-(U$11-Pad1)") (class "Default")
      (node (ref "U$11") (pin "1") (pinfunction "1_1") (pintype "bidirectional"))
    )
    (net (code "110") (name "unconnected-(U$11-Pad2)") (class "Default")
      (node (ref "U$11") (pin "2") (pinfunction "2_2") (pintype "bidirectional"))
    )
    (net (code "111") (name "unconnected-(U$11-Pad3)") (class "Default")
      (node (ref "U$11") (pin "3") (pinfunction "3_3") (pintype "bidirectional"))
    )
    (net (code "112") (name "unconnected-(U$11-Pad4)") (class "Default")
      (node (ref "U$11") (pin "4") (pinfunction "4_4") (pintype "bidirectional"))
    )
    (net (code "113") (name "unconnected-(U$11-Pad5)") (class "Default")
      (node (ref "U$11") (pin "5") (pinfunction "5_5") (pintype "bidirectional"))
    )
  )
)
